# expansioncard-template.net
KiCad netlist of a schematic drawn in EAGLE
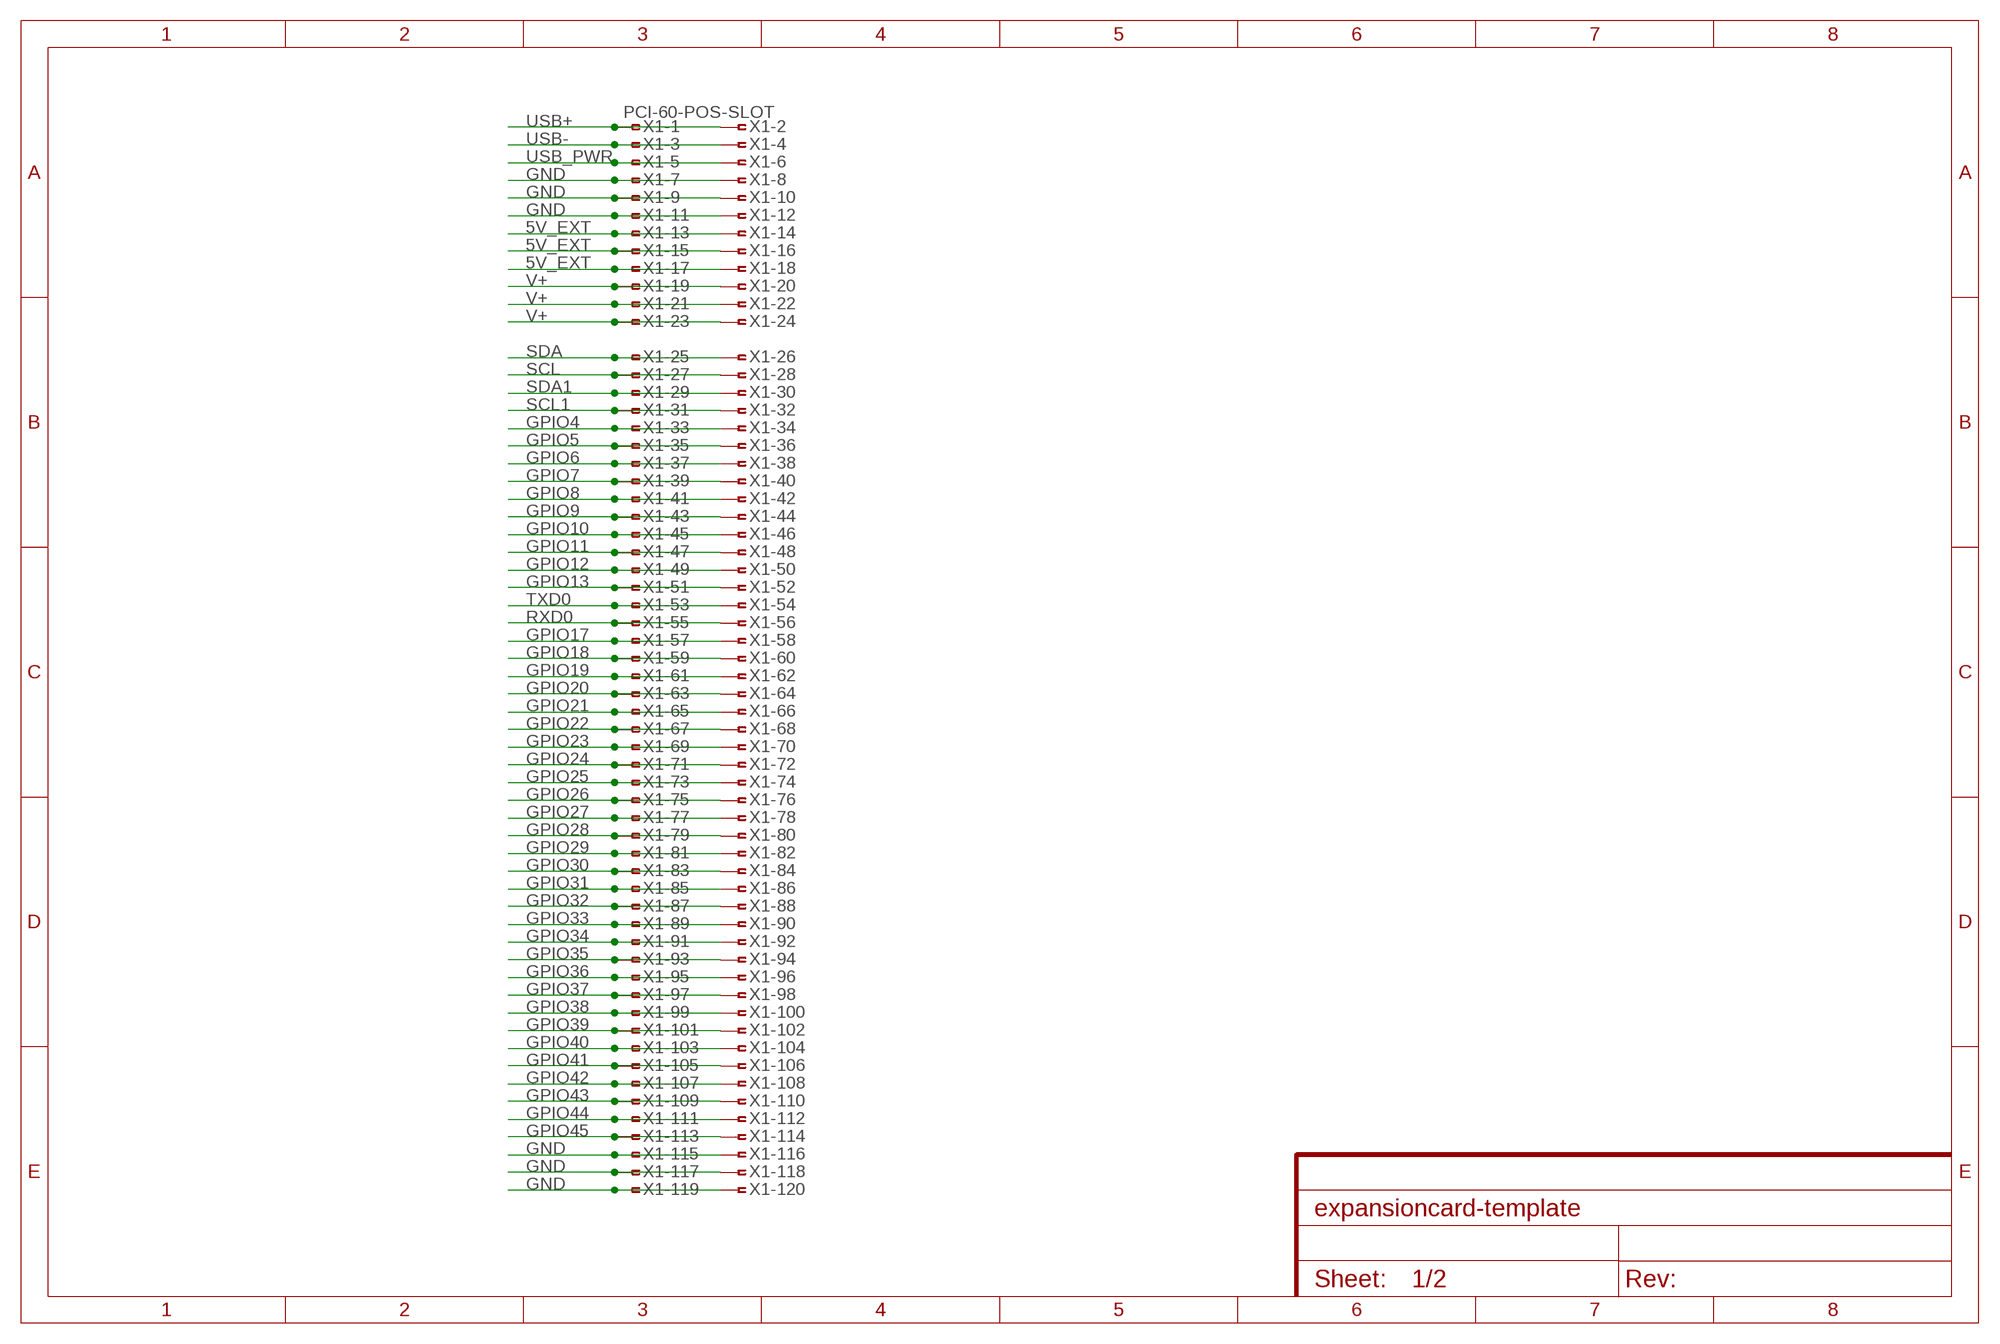
[diagram p0: schematic, sheet 1]
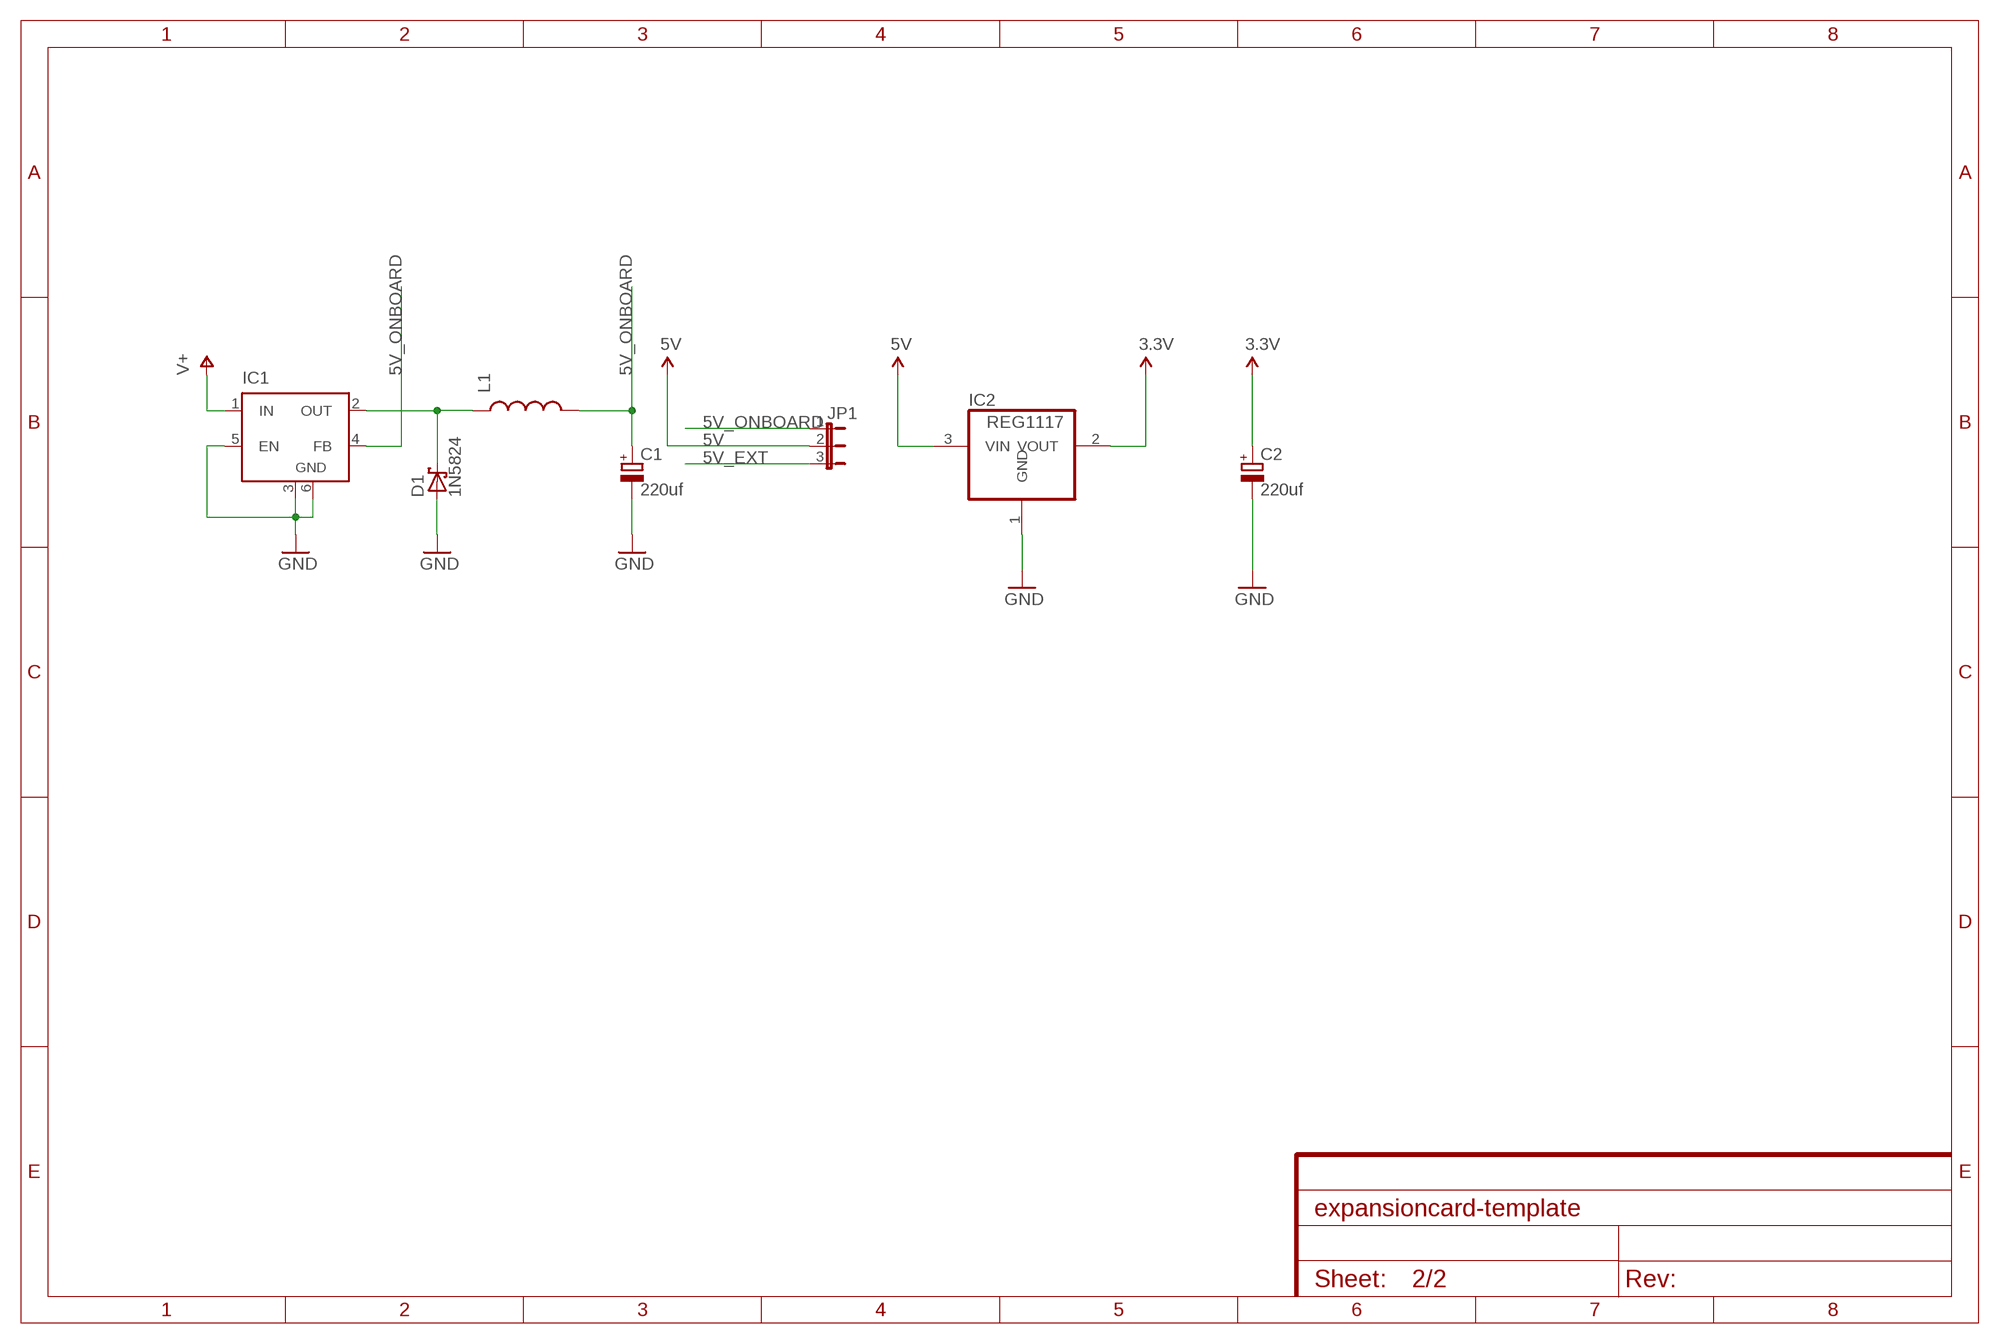
[diagram p1: schematic, sheet 2]

(export (version "E")
  (design (tool "Eeschema 10.0.6"))
  (components
    (comp (ref "X1")
      (value "PCI-60-POS-SLOT")
      (footprint "eagle-import:PCI-SLOT-60")
      (libsource (lib "eagle-import") (part "PCI-60-POS-SLOT"))
    )
    (comp (ref "C1")
      (value "220uf")
      (footprint "eagle-import:E2,5-6")
      (libsource (lib "eagle-import") (part "CPOL-EUE2.5-6"))
    )
    (comp (ref "C2")
      (value "220uf")
      (footprint "eagle-import:E2,5-6")
      (libsource (lib "eagle-import") (part "CPOL-EUE2.5-6"))
    )
    (comp (ref "D1")
      (value "1N5824")
      (footprint "eagle-import:DO41-7.6")
      (libsource (lib "eagle-import") (part "1N5817-B"))
    )
    (comp (ref "IC1")
      (value "LM2596S")
      (footprint "eagle-import:TO263-5")
      (libsource (lib "eagle-import") (part "LM2596S"))
    )
    (comp (ref "IC2")
      (value "REG1117")
      (footprint "eagle-import:SOT223")
      (libsource (lib "eagle-import") (part "REG1117"))
    )
    (comp (ref "JP1")
      (value "JP2E")
      (footprint "eagle-import:JP2")
      (libsource (lib "eagle-import") (part "JP2E"))
    )
    (comp (ref "L1")
      (value "INDUCTORSRU1038")
      (footprint "eagle-import:SRU1038")
      (libsource (lib "eagle-import") (part "INDUCTORSRU1038"))
    )
  )
  (nets
    (net (code "1") (name "3.3V") (class "Default")
      (node (ref "C2") (pin "+") (pinfunction "+_+") (pintype "passive"))
      (node (ref "IC2") (pin "2") (pinfunction "VOUT_2") (pintype "output"))
    )
    (net (code "2") (name "5V") (class "Default")
      (node (ref "IC2") (pin "3") (pinfunction "VIN_3") (pintype "input"))
      (node (ref "JP1") (pin "2") (pinfunction "2_2") (pintype "passive"))
    )
    (net (code "3") (name "5V_EXT") (class "Default")
      (node (ref "JP1") (pin "3") (pinfunction "3_3") (pintype "passive"))
      (node (ref "X1") (pin "13") (pinfunction "1_13") (pintype "passive"))
      (node (ref "X1") (pin "14") (pinfunction "1_14") (pintype "passive"))
      (node (ref "X1") (pin "15") (pinfunction "1_15") (pintype "passive"))
      (node (ref "X1") (pin "16") (pinfunction "1_16") (pintype "passive"))
      (node (ref "X1") (pin "17") (pinfunction "1_17") (pintype "passive"))
      (node (ref "X1") (pin "18") (pinfunction "1_18") (pintype "passive"))
    )
    (net (code "4") (name "5V_ONBOARD") (class "Default")
      (node (ref "C1") (pin "+") (pinfunction "+_+") (pintype "passive"))
      (node (ref "IC1") (pin "4") (pinfunction "FB_4") (pintype "input"))
      (node (ref "JP1") (pin "1") (pinfunction "1_1") (pintype "passive"))
      (node (ref "L1") (pin "2") (pinfunction "2_2") (pintype "passive"))
    )
    (net (code "5") (name "GND") (class "Default")
      (node (ref "C1") (pin "-") (pinfunction "-_-") (pintype "passive"))
      (node (ref "C2") (pin "-") (pinfunction "-_-") (pintype "passive"))
      (node (ref "D1") (pin "A") (pinfunction "A_A") (pintype "passive"))
      (node (ref "IC1") (pin "3") (pinfunction "GND_3") (pintype "power_in"))
      (node (ref "IC1") (pin "5") (pinfunction "EN_5") (pintype "input"))
      (node (ref "IC1") (pin "6") (pinfunction "GND_6") (pintype "power_in"))
      (node (ref "IC2") (pin "1") (pinfunction "GND_1") (pintype "power_in"))
      (node (ref "X1") (pin "10") (pinfunction "1_10") (pintype "passive"))
      (node (ref "X1") (pin "11") (pinfunction "1_11") (pintype "passive"))
      (node (ref "X1") (pin "115") (pinfunction "1_115") (pintype "passive"))
      (node (ref "X1") (pin "116") (pinfunction "1_116") (pintype "passive"))
      (node (ref "X1") (pin "117") (pinfunction "1_117") (pintype "passive"))
      (node (ref "X1") (pin "118") (pinfunction "1_118") (pintype "passive"))
      (node (ref "X1") (pin "119") (pinfunction "1_119") (pintype "passive"))
      (node (ref "X1") (pin "12") (pinfunction "1_12") (pintype "passive"))
      (node (ref "X1") (pin "120") (pinfunction "1_120") (pintype "passive"))
      (node (ref "X1") (pin "7") (pinfunction "1_7") (pintype "passive"))
      (node (ref "X1") (pin "8") (pinfunction "1_8") (pintype "passive"))
      (node (ref "X1") (pin "9") (pinfunction "1_9") (pintype "passive"))
    )
    (net (code "6") (name "GPIO4") (class "Default")
      (node (ref "X1") (pin "33") (pinfunction "1_33") (pintype "passive"))
      (node (ref "X1") (pin "34") (pinfunction "1_34") (pintype "passive"))
    )
    (net (code "7") (name "GPIO5") (class "Default")
      (node (ref "X1") (pin "35") (pinfunction "1_35") (pintype "passive"))
      (node (ref "X1") (pin "36") (pinfunction "1_36") (pintype "passive"))
    )
    (net (code "8") (name "GPIO6") (class "Default")
      (node (ref "X1") (pin "37") (pinfunction "1_37") (pintype "passive"))
      (node (ref "X1") (pin "38") (pinfunction "1_38") (pintype "passive"))
    )
    (net (code "9") (name "GPIO7") (class "Default")
      (node (ref "X1") (pin "39") (pinfunction "1_39") (pintype "passive"))
      (node (ref "X1") (pin "40") (pinfunction "1_40") (pintype "passive"))
    )
    (net (code "10") (name "GPIO8") (class "Default")
      (node (ref "X1") (pin "41") (pinfunction "1_41") (pintype "passive"))
      (node (ref "X1") (pin "42") (pinfunction "1_42") (pintype "passive"))
    )
    (net (code "11") (name "GPIO9") (class "Default")
      (node (ref "X1") (pin "43") (pinfunction "1_43") (pintype "passive"))
      (node (ref "X1") (pin "44") (pinfunction "1_44") (pintype "passive"))
    )
    (net (code "12") (name "GPIO10") (class "Default")
      (node (ref "X1") (pin "45") (pinfunction "1_45") (pintype "passive"))
      (node (ref "X1") (pin "46") (pinfunction "1_46") (pintype "passive"))
    )
    (net (code "13") (name "GPIO11") (class "Default")
      (node (ref "X1") (pin "47") (pinfunction "1_47") (pintype "passive"))
      (node (ref "X1") (pin "48") (pinfunction "1_48") (pintype "passive"))
    )
    (net (code "14") (name "GPIO12") (class "Default")
      (node (ref "X1") (pin "49") (pinfunction "1_49") (pintype "passive"))
      (node (ref "X1") (pin "50") (pinfunction "1_50") (pintype "passive"))
    )
    (net (code "15") (name "GPIO13") (class "Default")
      (node (ref "X1") (pin "51") (pinfunction "1_51") (pintype "passive"))
      (node (ref "X1") (pin "52") (pinfunction "1_52") (pintype "passive"))
    )
    (net (code "16") (name "GPIO17") (class "Default")
      (node (ref "X1") (pin "57") (pinfunction "1_57") (pintype "passive"))
      (node (ref "X1") (pin "58") (pinfunction "1_58") (pintype "passive"))
    )
    (net (code "17") (name "GPIO18") (class "Default")
      (node (ref "X1") (pin "59") (pinfunction "1_59") (pintype "passive"))
      (node (ref "X1") (pin "60") (pinfunction "1_60") (pintype "passive"))
    )
    (net (code "18") (name "GPIO19") (class "Default")
      (node (ref "X1") (pin "61") (pinfunction "1_61") (pintype "passive"))
      (node (ref "X1") (pin "62") (pinfunction "1_62") (pintype "passive"))
    )
    (net (code "19") (name "GPIO20") (class "Default")
      (node (ref "X1") (pin "63") (pinfunction "1_63") (pintype "passive"))
      (node (ref "X1") (pin "64") (pinfunction "1_64") (pintype "passive"))
    )
    (net (code "20") (name "GPIO21") (class "Default")
      (node (ref "X1") (pin "65") (pinfunction "1_65") (pintype "passive"))
      (node (ref "X1") (pin "66") (pinfunction "1_66") (pintype "passive"))
    )
    (net (code "21") (name "GPIO22") (class "Default")
      (node (ref "X1") (pin "67") (pinfunction "1_67") (pintype "passive"))
      (node (ref "X1") (pin "68") (pinfunction "1_68") (pintype "passive"))
    )
    (net (code "22") (name "GPIO23") (class "Default")
      (node (ref "X1") (pin "69") (pinfunction "1_69") (pintype "passive"))
      (node (ref "X1") (pin "70") (pinfunction "1_70") (pintype "passive"))
    )
    (net (code "23") (name "GPIO24") (class "Default")
      (node (ref "X1") (pin "71") (pinfunction "1_71") (pintype "passive"))
      (node (ref "X1") (pin "72") (pinfunction "1_72") (pintype "passive"))
    )
    (net (code "24") (name "GPIO25") (class "Default")
      (node (ref "X1") (pin "73") (pinfunction "1_73") (pintype "passive"))
      (node (ref "X1") (pin "74") (pinfunction "1_74") (pintype "passive"))
    )
    (net (code "25") (name "GPIO26") (class "Default")
      (node (ref "X1") (pin "75") (pinfunction "1_75") (pintype "passive"))
      (node (ref "X1") (pin "76") (pinfunction "1_76") (pintype "passive"))
    )
    (net (code "26") (name "GPIO27") (class "Default")
      (node (ref "X1") (pin "77") (pinfunction "1_77") (pintype "passive"))
      (node (ref "X1") (pin "78") (pinfunction "1_78") (pintype "passive"))
    )
    (net (code "27") (name "GPIO28") (class "Default")
      (node (ref "X1") (pin "79") (pinfunction "1_79") (pintype "passive"))
      (node (ref "X1") (pin "80") (pinfunction "1_80") (pintype "passive"))
    )
    (net (code "28") (name "GPIO29") (class "Default")
      (node (ref "X1") (pin "81") (pinfunction "1_81") (pintype "passive"))
      (node (ref "X1") (pin "82") (pinfunction "1_82") (pintype "passive"))
    )
    (net (code "29") (name "GPIO30") (class "Default")
      (node (ref "X1") (pin "83") (pinfunction "1_83") (pintype "passive"))
      (node (ref "X1") (pin "84") (pinfunction "1_84") (pintype "passive"))
    )
    (net (code "30") (name "GPIO31") (class "Default")
      (node (ref "X1") (pin "85") (pinfunction "1_85") (pintype "passive"))
      (node (ref "X1") (pin "86") (pinfunction "1_86") (pintype "passive"))
    )
    (net (code "31") (name "GPIO32") (class "Default")
      (node (ref "X1") (pin "87") (pinfunction "1_87") (pintype "passive"))
      (node (ref "X1") (pin "88") (pinfunction "1_88") (pintype "passive"))
    )
    (net (code "32") (name "GPIO33") (class "Default")
      (node (ref "X1") (pin "89") (pinfunction "1_89") (pintype "passive"))
      (node (ref "X1") (pin "90") (pinfunction "1_90") (pintype "passive"))
    )
    (net (code "33") (name "GPIO34") (class "Default")
      (node (ref "X1") (pin "91") (pinfunction "1_91") (pintype "passive"))
      (node (ref "X1") (pin "92") (pinfunction "1_92") (pintype "passive"))
    )
    (net (code "34") (name "GPIO35") (class "Default")
      (node (ref "X1") (pin "93") (pinfunction "1_93") (pintype "passive"))
      (node (ref "X1") (pin "94") (pinfunction "1_94") (pintype "passive"))
    )
    (net (code "35") (name "GPIO36") (class "Default")
      (node (ref "X1") (pin "95") (pinfunction "1_95") (pintype "passive"))
      (node (ref "X1") (pin "96") (pinfunction "1_96") (pintype "passive"))
    )
    (net (code "36") (name "GPIO37") (class "Default")
      (node (ref "X1") (pin "97") (pinfunction "1_97") (pintype "passive"))
      (node (ref "X1") (pin "98") (pinfunction "1_98") (pintype "passive"))
    )
    (net (code "37") (name "GPIO38") (class "Default")
      (node (ref "X1") (pin "100") (pinfunction "1_100") (pintype "passive"))
      (node (ref "X1") (pin "99") (pinfunction "1_99") (pintype "passive"))
    )
    (net (code "38") (name "GPIO39") (class "Default")
      (node (ref "X1") (pin "101") (pinfunction "1_101") (pintype "passive"))
      (node (ref "X1") (pin "102") (pinfunction "1_102") (pintype "passive"))
    )
    (net (code "39") (name "GPIO40") (class "Default")
      (node (ref "X1") (pin "103") (pinfunction "1_103") (pintype "passive"))
      (node (ref "X1") (pin "104") (pinfunction "1_104") (pintype "passive"))
    )
    (net (code "40") (name "GPIO41") (class "Default")
      (node (ref "X1") (pin "105") (pinfunction "1_105") (pintype "passive"))
      (node (ref "X1") (pin "106") (pinfunction "1_106") (pintype "passive"))
    )
    (net (code "41") (name "GPIO42") (class "Default")
      (node (ref "X1") (pin "107") (pinfunction "1_107") (pintype "passive"))
      (node (ref "X1") (pin "108") (pinfunction "1_108") (pintype "passive"))
    )
    (net (code "42") (name "GPIO43") (class "Default")
      (node (ref "X1") (pin "109") (pinfunction "1_109") (pintype "passive"))
      (node (ref "X1") (pin "110") (pinfunction "1_110") (pintype "passive"))
    )
    (net (code "43") (name "GPIO44") (class "Default")
      (node (ref "X1") (pin "111") (pinfunction "1_111") (pintype "passive"))
      (node (ref "X1") (pin "112") (pinfunction "1_112") (pintype "passive"))
    )
    (net (code "44") (name "GPIO45") (class "Default")
      (node (ref "X1") (pin "113") (pinfunction "1_113") (pintype "passive"))
      (node (ref "X1") (pin "114") (pinfunction "1_114") (pintype "passive"))
    )
    (net (code "45") (name "Net-(IC1-OUT)") (class "Default")
      (node (ref "D1") (pin "C") (pinfunction "C_C") (pintype "passive"))
      (node (ref "IC1") (pin "2") (pinfunction "OUT_2") (pintype "output"))
      (node (ref "L1") (pin "1") (pinfunction "1_1") (pintype "passive"))
    )
    (net (code "46") (name "RXD0") (class "Default")
      (node (ref "X1") (pin "55") (pinfunction "1_55") (pintype "passive"))
      (node (ref "X1") (pin "56") (pinfunction "1_56") (pintype "passive"))
    )
    (net (code "47") (name "SCL") (class "Default")
      (node (ref "X1") (pin "27") (pinfunction "1_27") (pintype "passive"))
      (node (ref "X1") (pin "28") (pinfunction "1_28") (pintype "passive"))
    )
    (net (code "48") (name "SCL1") (class "Default")
      (node (ref "X1") (pin "31") (pinfunction "1_31") (pintype "passive"))
      (node (ref "X1") (pin "32") (pinfunction "1_32") (pintype "passive"))
    )
    (net (code "49") (name "SDA") (class "Default")
      (node (ref "X1") (pin "25") (pinfunction "1_25") (pintype "passive"))
      (node (ref "X1") (pin "26") (pinfunction "1_26") (pintype "passive"))
    )
    (net (code "50") (name "SDA1") (class "Default")
      (node (ref "X1") (pin "29") (pinfunction "1_29") (pintype "passive"))
      (node (ref "X1") (pin "30") (pinfunction "1_30") (pintype "passive"))
    )
    (net (code "51") (name "TXD0") (class "Default")
      (node (ref "X1") (pin "53") (pinfunction "1_53") (pintype "passive"))
      (node (ref "X1") (pin "54") (pinfunction "1_54") (pintype "passive"))
    )
    (net (code "52") (name "USB+") (class "Default")
      (node (ref "X1") (pin "1") (pinfunction "1_1") (pintype "passive"))
      (node (ref "X1") (pin "2") (pinfunction "1_2") (pintype "passive"))
    )
    (net (code "53") (name "USB-") (class "Default")
      (node (ref "X1") (pin "3") (pinfunction "1_3") (pintype "passive"))
      (node (ref "X1") (pin "4") (pinfunction "1_4") (pintype "passive"))
    )
    (net (code "54") (name "USB_PWR") (class "Default")
      (node (ref "X1") (pin "5") (pinfunction "1_5") (pintype "passive"))
      (node (ref "X1") (pin "6") (pinfunction "1_6") (pintype "passive"))
    )
    (net (code "55") (name "V+") (class "Default")
      (node (ref "IC1") (pin "1") (pinfunction "IN_1") (pintype "input"))
      (node (ref "X1") (pin "19") (pinfunction "1_19") (pintype "passive"))
      (node (ref "X1") (pin "20") (pinfunction "1_20") (pintype "passive"))
      (node (ref "X1") (pin "21") (pinfunction "1_21") (pintype "passive"))
      (node (ref "X1") (pin "22") (pinfunction "1_22") (pintype "passive"))
      (node (ref "X1") (pin "23") (pinfunction "1_23") (pintype "passive"))
      (node (ref "X1") (pin "24") (pinfunction "1_24") (pintype "passive"))
    )
  )
)
